# Resolver_fuses.net
KiCad netlist of a schematic drawn in Altium Designer
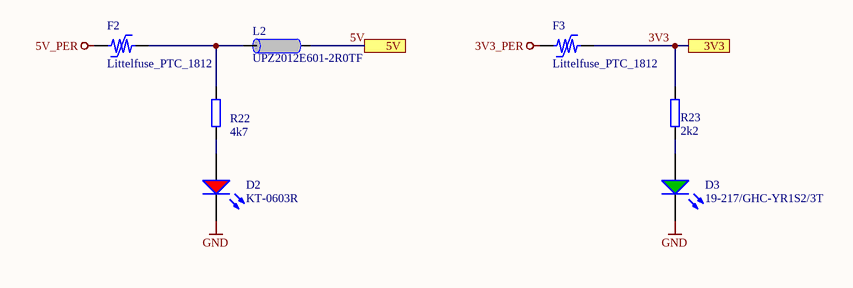
[diagram p0: Resolver fuses.SchDoc]

(export (version "E")
  (design (tool "Eeschema 10.0.6"))
  (components
    (comp (ref "D2")
      (value "KT-0603R")
      (footprint "WL-SMCW_0603")
      (description "LED RED 520~625NM 90~100MCD@20MA TOP VIEW 0603 ROHS")
      (fields
        (field (name "MANUFACTURER") "Hubei KENTO Elec")
        (field (name "LCSC PART NUMBER") "C2286")
        (field (name "CREATED FROM") "T. Wendt")
      )
      (libsource (lib "user") (part "LED_Red"))
    )
    (comp (ref "D3")
      (value "19-217/GHC-YR1S2/3T")
      (footprint "WL-SMCW_0603")
      (description "LED GREEN 520~535NM 112~258MCD@20MA TOP VIEW 0603 ROHS")
      (fields
        (field (name "MANUFACTURER") "Everlight Elec")
        (field (name "LCSC PART NUMBER") "C72043")
        (field (name "CREATED FROM") "T. Wendt")
      )
      (libsource (lib "user") (part "LED_Green"))
    )
    (comp (ref "F2")
      (value "Littelfuse_PTC_1812")
      (footprint "1812_PTC_Polyfuse_Littelfuse")
      (description "POLYSWITCH RESETTABLE DEVICES")
      (fields
        (field (name "MPN") "miniASMDC110F/24")
        (field (name "MF") "Littelfuse")
        (field (name "CREATED") "2019_02_10_AGeiger")
        (field (name "CREATED FROM") "MHlatky")
      )
      (libsource (lib "user") (part "Littelfuse_PTC_1812"))
    )
    (comp (ref "F3")
      (value "Littelfuse_PTC_1812")
      (footprint "1812_PTC_Polyfuse_Littelfuse")
      (description "POLYSWITCH RESETTABLE DEVICES")
      (fields
        (field (name "MPN") "miniASMDC110F/24")
        (field (name "MF") "Littelfuse")
        (field (name "CREATED") "2019_02_10_AGeiger")
        (field (name "CREATED FROM") "MHlatky")
      )
      (libsource (lib "user") (part "Littelfuse_PTC_1812"))
    )
    (comp (ref "L2")
      (value "UPZ2012E601-2R0TF")
      (footprint "INDC2012X92N_V")
      (description "2A 1 90mΩ 600Ω@100MHz ±25% 0805  Ferrite Beads ROHS")
      (fields
        (field (name "MANUFACTURER") "Sunlord")
        (field (name "LCSC PART NUMBER") "C98308")
        (field (name "CREATED FROM") "AGeiger")
      )
      (libsource (lib "user") (part "Ferrite_Bead"))
    )
    (comp (ref "R22")
      (value "4k7")
      (footprint "RES 0603_1608")
      (description "SMD resistor E24 series")
      (fields
        (field (name "MANUFACTURER PART NUMBER") "0603WAF4701T5E")
        (field (name "MANUFACTURER") "UNI-ROYAL")
        (field (name "CREATED FROM") "AGeiger")
      )
      (libsource (lib "user") (part "Resistor"))
    )
    (comp (ref "R23")
      (value "2k2")
      (footprint "RES 0603_1608")
      (description "SMD resistor E24 series")
      (fields
        (field (name "MANUFACTURER PART NUMBER") "RK73B1JTTD222J")
        (field (name "MANUFACTURER") "KOA Speer")
        (field (name "CREATED FROM") "MGremer")
      )
      (libsource (lib "user") (part "Resistor"))
    )
  )
  (nets
    (net (code "1") (name "/3V3") (class "Default")
      (node (ref "F3") (pin "2") (pinfunction "2_2") (pintype "passive"))
      (node (ref "R23") (pin "2") (pinfunction "2_2") (pintype "passive"))
    )
    (net (code "2") (name "/5V") (class "Default")
      (node (ref "L2") (pin "1") (pinfunction "1_1") (pintype "passive"))
    )
    (net (code "3") (name "3V3_PER") (class "Default")
      (node (ref "F3") (pin "1") (pinfunction "1_1") (pintype "passive"))
    )
    (net (code "4") (name "5V_PER") (class "Default")
      (node (ref "F2") (pin "1") (pinfunction "1_1") (pintype "passive"))
    )
    (net (code "5") (name "GND") (class "Default")
      (node (ref "D2") (pin "1") (pinfunction "K_1") (pintype "passive"))
      (node (ref "D3") (pin "1") (pinfunction "K_1") (pintype "passive"))
    )
    (net (code "6") (name "Net-(D2-A)") (class "Default")
      (node (ref "D2") (pin "2") (pinfunction "A_2") (pintype "passive"))
      (node (ref "R22") (pin "1") (pinfunction "1_1") (pintype "passive"))
    )
    (net (code "7") (name "Net-(D3-A)") (class "Default")
      (node (ref "D3") (pin "2") (pinfunction "A_2") (pintype "passive"))
      (node (ref "R23") (pin "1") (pinfunction "1_1") (pintype "passive"))
    )
    (net (code "8") (name "Net-(F2-Pad2)") (class "Default")
      (node (ref "F2") (pin "2") (pinfunction "2_2") (pintype "passive"))
      (node (ref "L2") (pin "2") (pinfunction "2_2") (pintype "passive"))
      (node (ref "R22") (pin "2") (pinfunction "2_2") (pintype "passive"))
    )
  )
)
